# v5_compact.net
KiCad netlist of a schematic drawn in EAGLE
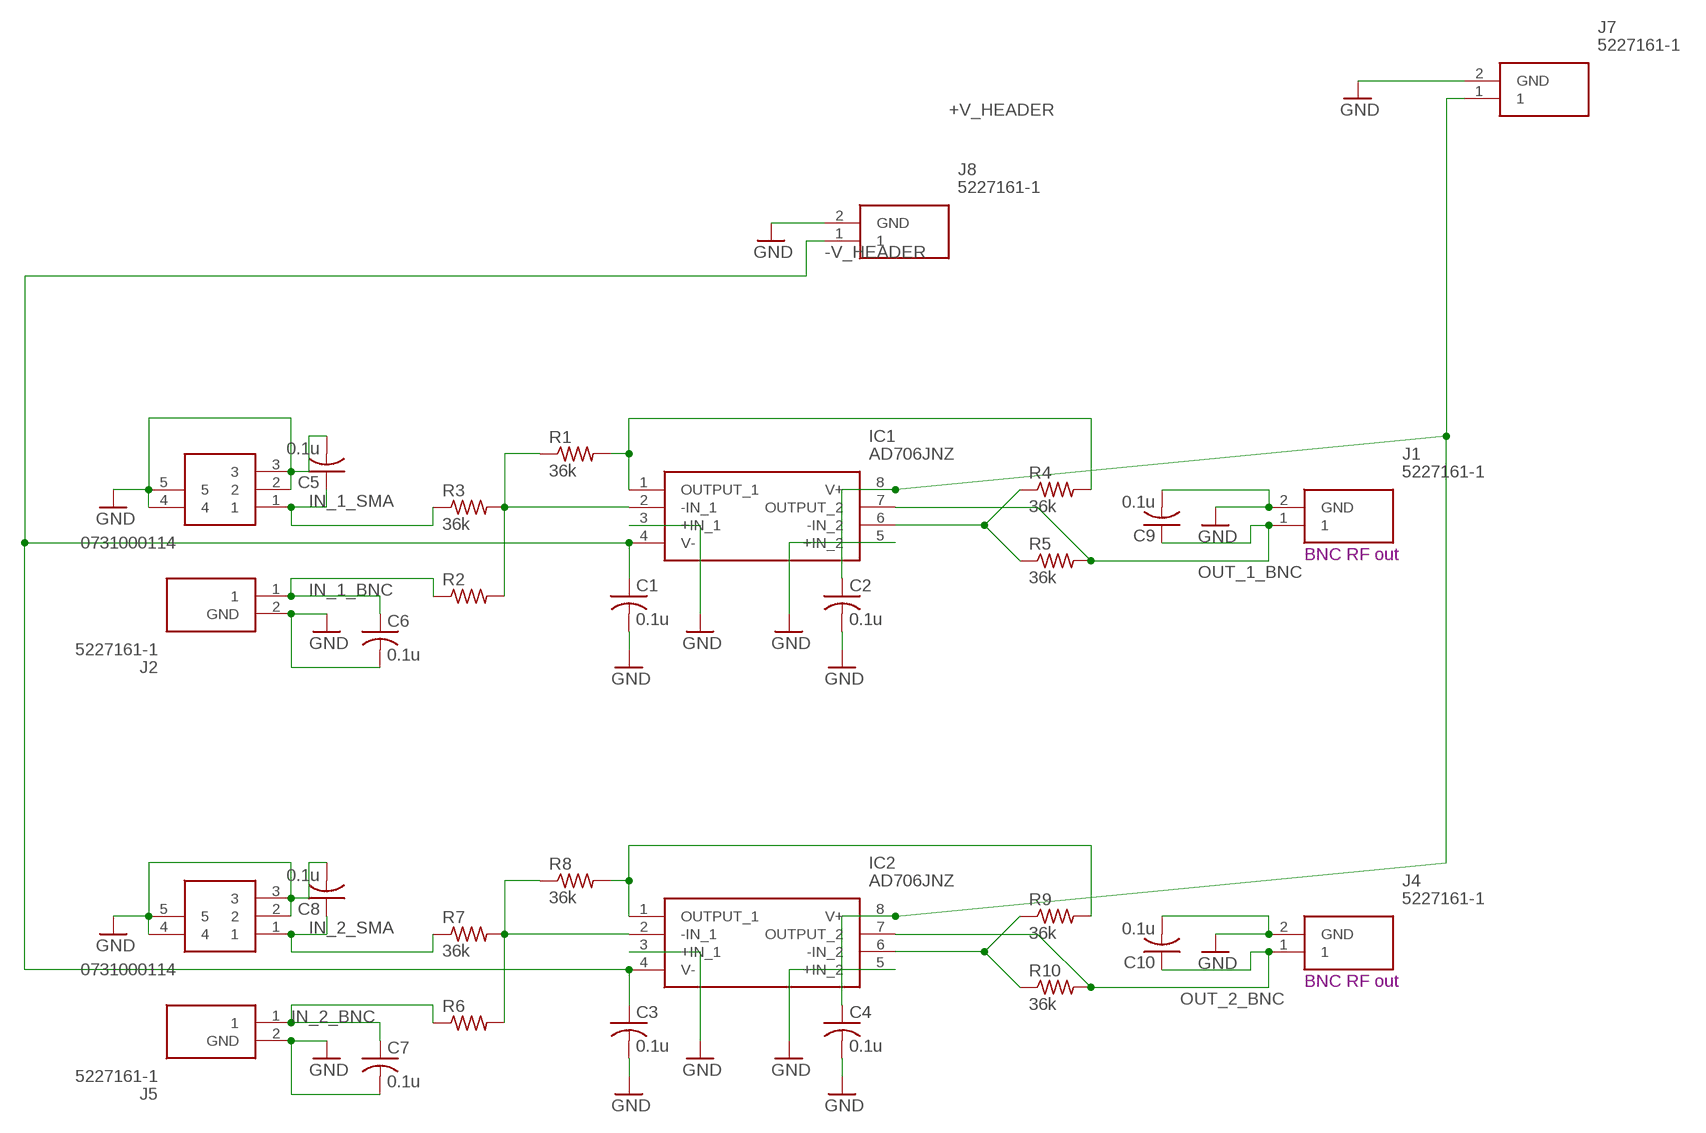
[diagram p0: schematic, sheet 1]

(export (version "E")
  (design (tool "Eeschema 10.0.6"))
  (components
    (comp (ref "C1")
      (value "0.1u")
      (footprint "eagle-import:C050-025X075")
      (libsource (lib "eagle-import") (part "C-US050-025X075"))
    )
    (comp (ref "C2")
      (value "0.1u")
      (footprint "eagle-import:C050-025X075")
      (libsource (lib "eagle-import") (part "C-US050-025X075"))
    )
    (comp (ref "C3")
      (value "0.1u")
      (footprint "eagle-import:C050-025X075")
      (libsource (lib "eagle-import") (part "C-US050-025X075"))
    )
    (comp (ref "C4")
      (value "0.1u")
      (footprint "eagle-import:C050-025X075")
      (libsource (lib "eagle-import") (part "C-US050-025X075"))
    )
    (comp (ref "C5")
      (value "0.1u")
      (footprint "eagle-import:C050-025X075")
      (libsource (lib "eagle-import") (part "C-US050-025X075"))
    )
    (comp (ref "C6")
      (value "0.1u")
      (footprint "eagle-import:C050-025X075")
      (libsource (lib "eagle-import") (part "C-US050-025X075"))
    )
    (comp (ref "C7")
      (value "0.1u")
      (footprint "eagle-import:C050-025X075")
      (libsource (lib "eagle-import") (part "C-US050-025X075"))
    )
    (comp (ref "C8")
      (value "0.1u")
      (footprint "eagle-import:C050-025X075")
      (libsource (lib "eagle-import") (part "C-US050-025X075"))
    )
    (comp (ref "C9")
      (value "0.1u")
      (footprint "eagle-import:C050-025X075")
      (libsource (lib "eagle-import") (part "C-US050-025X075"))
    )
    (comp (ref "C10")
      (value "0.1u")
      (footprint "eagle-import:C050-025X075")
      (libsource (lib "eagle-import") (part "C-US050-025X075"))
    )
    (comp (ref "IC1")
      (value "AD706JNZ")
      (footprint "eagle-import:DIP794W56P254L959H533Q8N")
      (fields (field (name "MOUSER_PART_NUMBER") "584-AD706JNZ"))
      (libsource (lib "eagle-import") (part "AD706JNZ"))
    )
    (comp (ref "IC2")
      (value "AD706JNZ")
      (footprint "eagle-import:DIP794W56P254L959H533Q8N")
      (fields (field (name "MOUSER_PART_NUMBER") "584-AD706JNZ"))
      (libsource (lib "eagle-import") (part "AD706JNZ"))
    )
    (comp (ref "J1")
      (value "5227161-1")
      (footprint "eagle-import:52271611")
      (fields (field (name "MOUSER_PART_NUMBER") "571-5227161-1"))
      (libsource (lib "eagle-import") (part "5227161-1"))
    )
    (comp (ref "J2")
      (value "5227161-1")
      (footprint "eagle-import:52271611")
      (fields (field (name "MOUSER_PART_NUMBER") "571-5227161-1"))
      (libsource (lib "eagle-import") (part "5227161-1"))
    )
    (comp (ref "J3")
      (value "0731000114")
      (footprint "eagle-import:0731000114")
      (libsource (lib "eagle-import") (part "0731000114"))
    )
    (comp (ref "J4")
      (value "5227161-1")
      (footprint "eagle-import:52271611")
      (fields (field (name "MOUSER_PART_NUMBER") "571-5227161-1"))
      (libsource (lib "eagle-import") (part "5227161-1"))
    )
    (comp (ref "J5")
      (value "5227161-1")
      (footprint "eagle-import:52271611")
      (fields (field (name "MOUSER_PART_NUMBER") "571-5227161-1"))
      (libsource (lib "eagle-import") (part "5227161-1"))
    )
    (comp (ref "J6")
      (value "0731000114")
      (footprint "eagle-import:0731000114")
      (libsource (lib "eagle-import") (part "0731000114"))
    )
    (comp (ref "J7")
      (value "5227161-1")
      (footprint "eagle-import:52271611")
      (fields (field (name "MOUSER_PART_NUMBER") "571-5227161-1"))
      (libsource (lib "eagle-import") (part "5227161-1"))
    )
    (comp (ref "J8")
      (value "5227161-1")
      (footprint "eagle-import:52271611")
      (fields (field (name "MOUSER_PART_NUMBER") "571-5227161-1"))
      (libsource (lib "eagle-import") (part "5227161-1"))
    )
    (comp (ref "R1")
      (value "36k")
      (footprint "eagle-import:0207_10")
      (libsource (lib "eagle-import") (part "R-US_0207/10"))
    )
    (comp (ref "R2")
      (value "R-US_0207/10")
      (footprint "eagle-import:0207_10")
      (libsource (lib "eagle-import") (part "R-US_0207/10"))
    )
    (comp (ref "R3")
      (value "36k")
      (footprint "eagle-import:0207_10")
      (libsource (lib "eagle-import") (part "R-US_0207/10"))
    )
    (comp (ref "R4")
      (value "36k")
      (footprint "eagle-import:0207_10")
      (libsource (lib "eagle-import") (part "R-US_0207/10"))
    )
    (comp (ref "R5")
      (value "36k")
      (footprint "eagle-import:0207_10")
      (libsource (lib "eagle-import") (part "R-US_0207/10"))
    )
    (comp (ref "R6")
      (value "R-US_0207/10")
      (footprint "eagle-import:0207_10")
      (libsource (lib "eagle-import") (part "R-US_0207/10"))
    )
    (comp (ref "R7")
      (value "36k")
      (footprint "eagle-import:0207_10")
      (libsource (lib "eagle-import") (part "R-US_0207/10"))
    )
    (comp (ref "R8")
      (value "36k")
      (footprint "eagle-import:0207_10")
      (libsource (lib "eagle-import") (part "R-US_0207/10"))
    )
    (comp (ref "R9")
      (value "36k")
      (footprint "eagle-import:0207_10")
      (libsource (lib "eagle-import") (part "R-US_0207/10"))
    )
    (comp (ref "R10")
      (value "36k")
      (footprint "eagle-import:0207_10")
      (libsource (lib "eagle-import") (part "R-US_0207/10"))
    )
  )
  (nets
    (net (code "1") (name "/+V_HEADER") (class "Default")
      (node (ref "C2") (pin "1") (pinfunction "1_1") (pintype "passive"))
      (node (ref "C4") (pin "1") (pinfunction "1_1") (pintype "passive"))
      (node (ref "IC1") (pin "8") (pinfunction "V+_8") (pintype "bidirectional"))
      (node (ref "IC2") (pin "8") (pinfunction "V+_8") (pintype "bidirectional"))
      (node (ref "J7") (pin "1") (pinfunction "1_1") (pintype "bidirectional"))
    )
    (net (code "2") (name "/-V_HEADER") (class "Default")
      (node (ref "C1") (pin "1") (pinfunction "1_1") (pintype "passive"))
      (node (ref "C3") (pin "1") (pinfunction "1_1") (pintype "passive"))
      (node (ref "IC1") (pin "4") (pinfunction "V-_4") (pintype "bidirectional"))
      (node (ref "IC2") (pin "4") (pinfunction "V-_4") (pintype "bidirectional"))
      (node (ref "J8") (pin "1") (pinfunction "1_1") (pintype "bidirectional"))
    )
    (net (code "3") (name "/IN_1_BNC") (class "Default")
      (node (ref "C6") (pin "1") (pinfunction "1_1") (pintype "passive"))
      (node (ref "J2") (pin "1") (pinfunction "1_1") (pintype "bidirectional"))
      (node (ref "R2") (pin "1") (pinfunction "1_1") (pintype "passive"))
    )
    (net (code "4") (name "/IN_1_SMA") (class "Default")
      (node (ref "C5") (pin "1") (pinfunction "1_1") (pintype "passive"))
      (node (ref "J3") (pin "1") (pinfunction "1_1") (pintype "bidirectional"))
      (node (ref "R3") (pin "1") (pinfunction "1_1") (pintype "passive"))
    )
    (net (code "5") (name "/IN_2_BNC") (class "Default")
      (node (ref "C7") (pin "1") (pinfunction "1_1") (pintype "passive"))
      (node (ref "J5") (pin "1") (pinfunction "1_1") (pintype "bidirectional"))
      (node (ref "R6") (pin "1") (pinfunction "1_1") (pintype "passive"))
    )
    (net (code "6") (name "/IN_2_SMA") (class "Default")
      (node (ref "C8") (pin "1") (pinfunction "1_1") (pintype "passive"))
      (node (ref "J6") (pin "1") (pinfunction "1_1") (pintype "bidirectional"))
      (node (ref "R7") (pin "1") (pinfunction "1_1") (pintype "passive"))
    )
    (net (code "7") (name "/OUT_1_BNC") (class "Default")
      (node (ref "C9") (pin "1") (pinfunction "1_1") (pintype "passive"))
      (node (ref "IC1") (pin "7") (pinfunction "OUTPUT_2_7") (pintype "bidirectional"))
      (node (ref "J1") (pin "1") (pinfunction "1_1") (pintype "bidirectional"))
      (node (ref "R5") (pin "2") (pinfunction "2_2") (pintype "passive"))
    )
    (net (code "8") (name "/OUT_2_BNC") (class "Default")
      (node (ref "C10") (pin "1") (pinfunction "1_1") (pintype "passive"))
      (node (ref "IC2") (pin "7") (pinfunction "OUTPUT_2_7") (pintype "bidirectional"))
      (node (ref "J4") (pin "1") (pinfunction "1_1") (pintype "bidirectional"))
      (node (ref "R10") (pin "2") (pinfunction "2_2") (pintype "passive"))
    )
    (net (code "9") (name "GND") (class "Default")
      (node (ref "C1") (pin "2") (pinfunction "2_2") (pintype "passive"))
      (node (ref "C10") (pin "2") (pinfunction "2_2") (pintype "passive"))
      (node (ref "C2") (pin "2") (pinfunction "2_2") (pintype "passive"))
      (node (ref "C3") (pin "2") (pinfunction "2_2") (pintype "passive"))
      (node (ref "C4") (pin "2") (pinfunction "2_2") (pintype "passive"))
      (node (ref "C5") (pin "2") (pinfunction "2_2") (pintype "passive"))
      (node (ref "C6") (pin "2") (pinfunction "2_2") (pintype "passive"))
      (node (ref "C7") (pin "2") (pinfunction "2_2") (pintype "passive"))
      (node (ref "C8") (pin "2") (pinfunction "2_2") (pintype "passive"))
      (node (ref "C9") (pin "2") (pinfunction "2_2") (pintype "passive"))
      (node (ref "IC1") (pin "3") (pinfunction "+IN_1_3") (pintype "bidirectional"))
      (node (ref "IC1") (pin "5") (pinfunction "+IN_2_5") (pintype "bidirectional"))
      (node (ref "IC2") (pin "3") (pinfunction "+IN_1_3") (pintype "bidirectional"))
      (node (ref "IC2") (pin "5") (pinfunction "+IN_2_5") (pintype "bidirectional"))
      (node (ref "J1") (pin "2") (pinfunction "GND_2") (pintype "bidirectional"))
      (node (ref "J2") (pin "2") (pinfunction "GND_2") (pintype "bidirectional"))
      (node (ref "J3") (pin "2") (pinfunction "2_2") (pintype "bidirectional"))
      (node (ref "J3") (pin "3") (pinfunction "3_3") (pintype "bidirectional"))
      (node (ref "J3") (pin "4") (pinfunction "4_4") (pintype "bidirectional"))
      (node (ref "J3") (pin "5") (pinfunction "5_5") (pintype "bidirectional"))
      (node (ref "J4") (pin "2") (pinfunction "GND_2") (pintype "bidirectional"))
      (node (ref "J5") (pin "2") (pinfunction "GND_2") (pintype "bidirectional"))
      (node (ref "J6") (pin "2") (pinfunction "2_2") (pintype "bidirectional"))
      (node (ref "J6") (pin "3") (pinfunction "3_3") (pintype "bidirectional"))
      (node (ref "J6") (pin "4") (pinfunction "4_4") (pintype "bidirectional"))
      (node (ref "J6") (pin "5") (pinfunction "5_5") (pintype "bidirectional"))
      (node (ref "J7") (pin "2") (pinfunction "GND_2") (pintype "bidirectional"))
      (node (ref "J8") (pin "2") (pinfunction "GND_2") (pintype "bidirectional"))
    )
    (net (code "10") (name "Net-(IC1--IN_1)") (class "Default")
      (node (ref "IC1") (pin "2") (pinfunction "-IN_1_2") (pintype "bidirectional"))
      (node (ref "R1") (pin "1") (pinfunction "1_1") (pintype "passive"))
      (node (ref "R2") (pin "2") (pinfunction "2_2") (pintype "passive"))
      (node (ref "R3") (pin "2") (pinfunction "2_2") (pintype "passive"))
    )
    (net (code "11") (name "Net-(IC1--IN_2)") (class "Default")
      (node (ref "IC1") (pin "6") (pinfunction "-IN_2_6") (pintype "bidirectional"))
      (node (ref "R4") (pin "1") (pinfunction "1_1") (pintype "passive"))
      (node (ref "R5") (pin "1") (pinfunction "1_1") (pintype "passive"))
    )
    (net (code "12") (name "Net-(IC1-OUTPUT_1)") (class "Default")
      (node (ref "IC1") (pin "1") (pinfunction "OUTPUT_1_1") (pintype "bidirectional"))
      (node (ref "R1") (pin "2") (pinfunction "2_2") (pintype "passive"))
      (node (ref "R4") (pin "2") (pinfunction "2_2") (pintype "passive"))
    )
    (net (code "13") (name "Net-(IC2--IN_1)") (class "Default")
      (node (ref "IC2") (pin "2") (pinfunction "-IN_1_2") (pintype "bidirectional"))
      (node (ref "R6") (pin "2") (pinfunction "2_2") (pintype "passive"))
      (node (ref "R7") (pin "2") (pinfunction "2_2") (pintype "passive"))
      (node (ref "R8") (pin "1") (pinfunction "1_1") (pintype "passive"))
    )
    (net (code "14") (name "Net-(IC2--IN_2)") (class "Default")
      (node (ref "IC2") (pin "6") (pinfunction "-IN_2_6") (pintype "bidirectional"))
      (node (ref "R10") (pin "1") (pinfunction "1_1") (pintype "passive"))
      (node (ref "R9") (pin "1") (pinfunction "1_1") (pintype "passive"))
    )
    (net (code "15") (name "Net-(IC2-OUTPUT_1)") (class "Default")
      (node (ref "IC2") (pin "1") (pinfunction "OUTPUT_1_1") (pintype "bidirectional"))
      (node (ref "R8") (pin "2") (pinfunction "2_2") (pintype "passive"))
      (node (ref "R9") (pin "2") (pinfunction "2_2") (pintype "passive"))
    )
  )
)
